# XIAO_ESP32S3_Exp_Board_v1_0.net
KiCad netlist of a schematic drawn in EAGLE
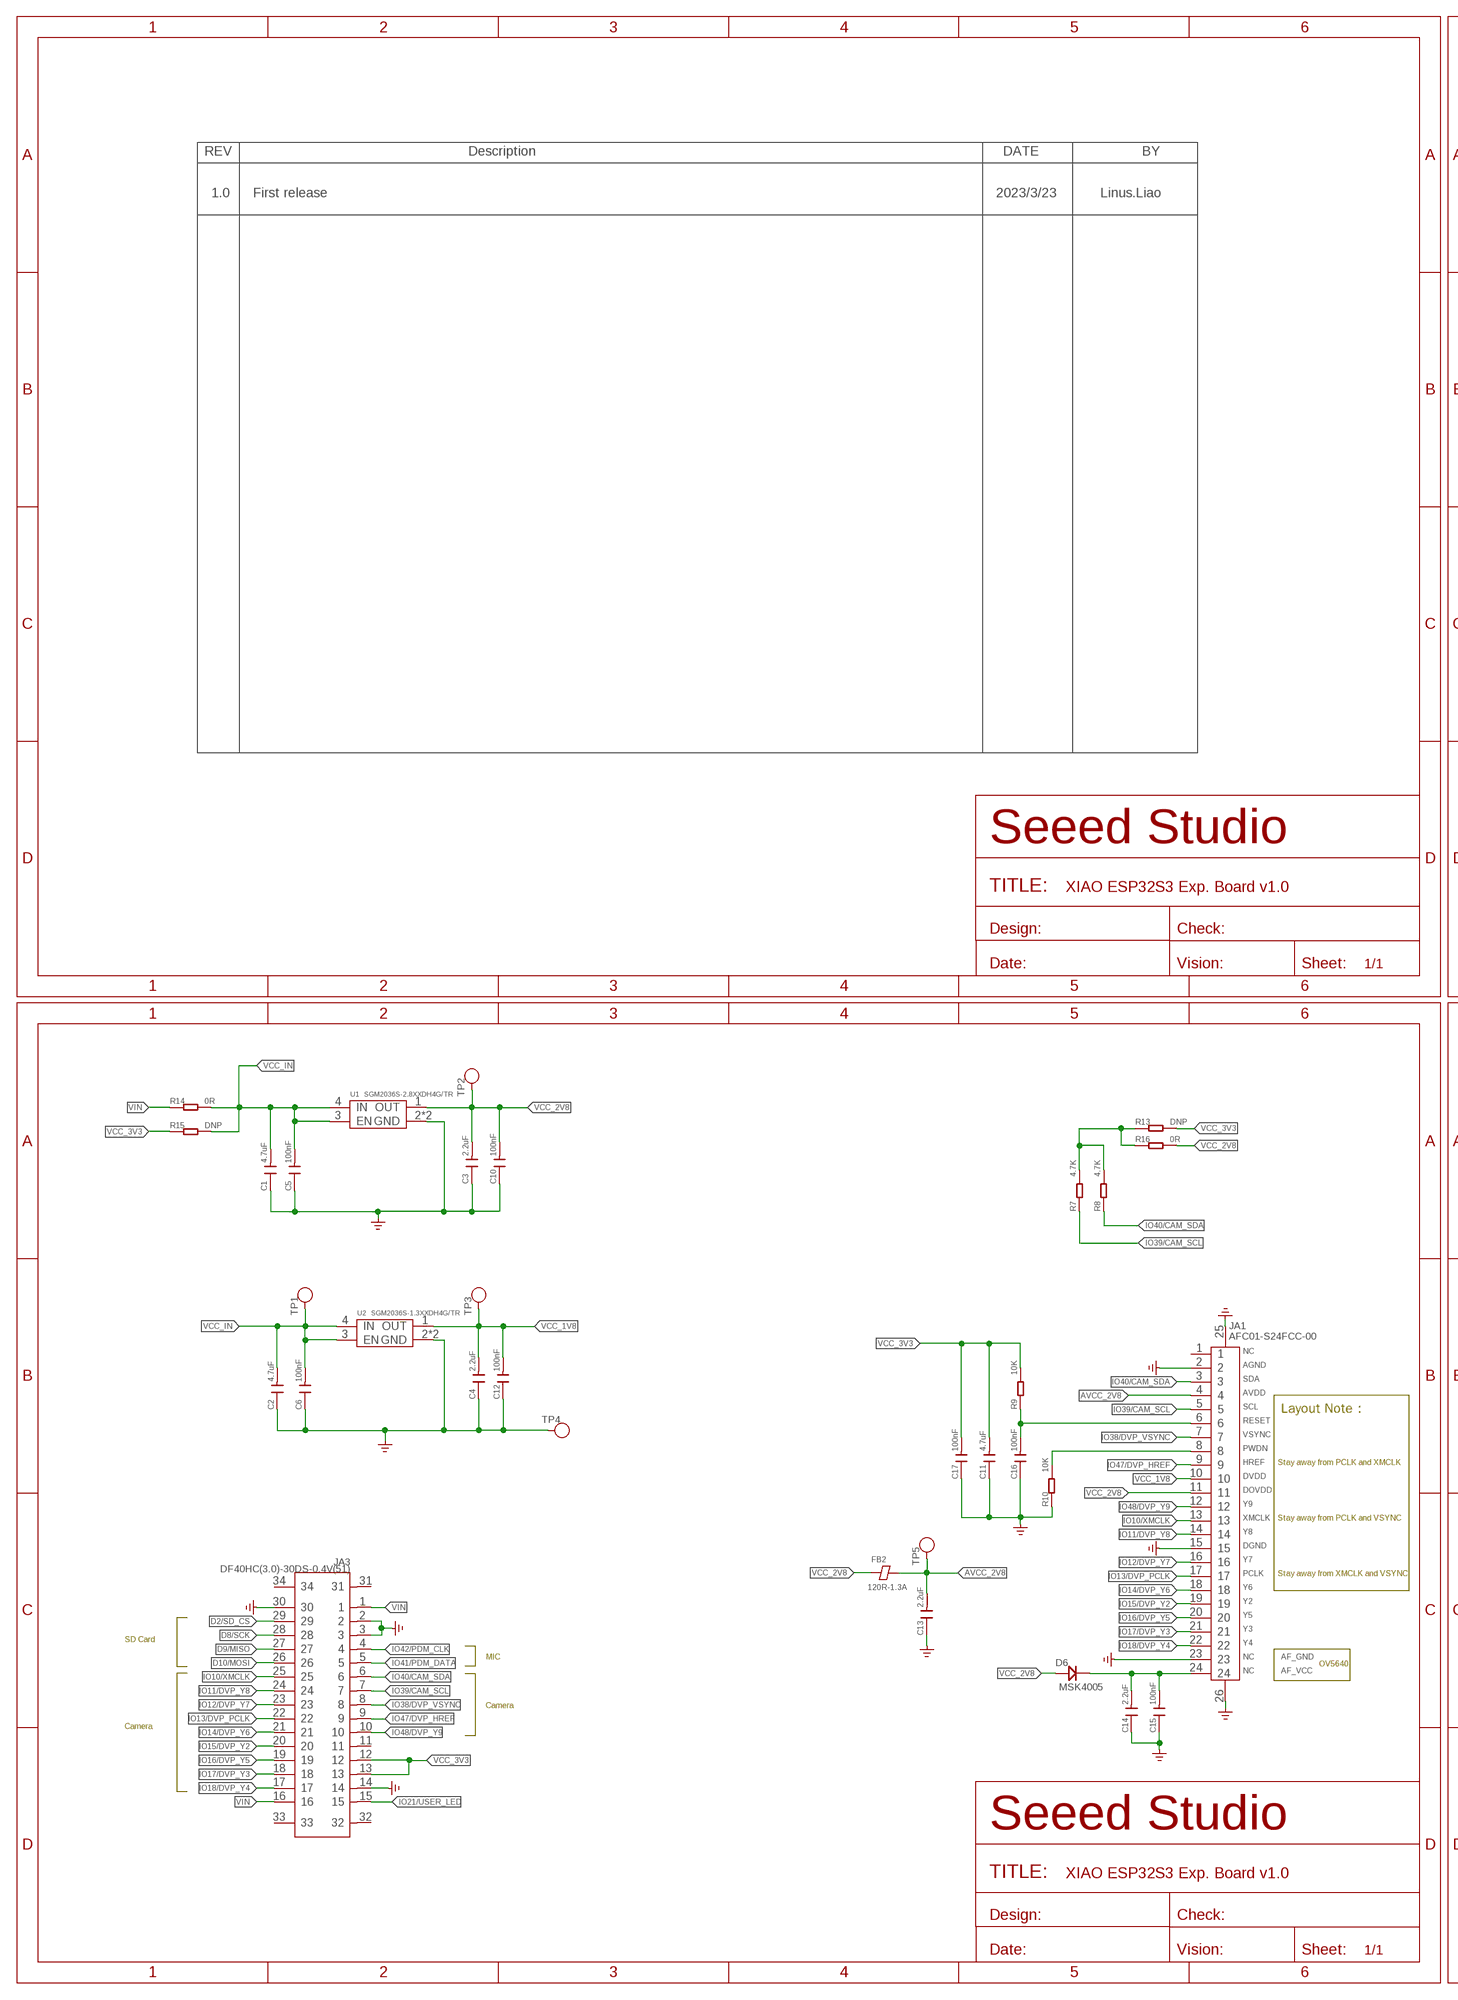
[diagram p0: schematic, sheet 1, part 1 of 2]
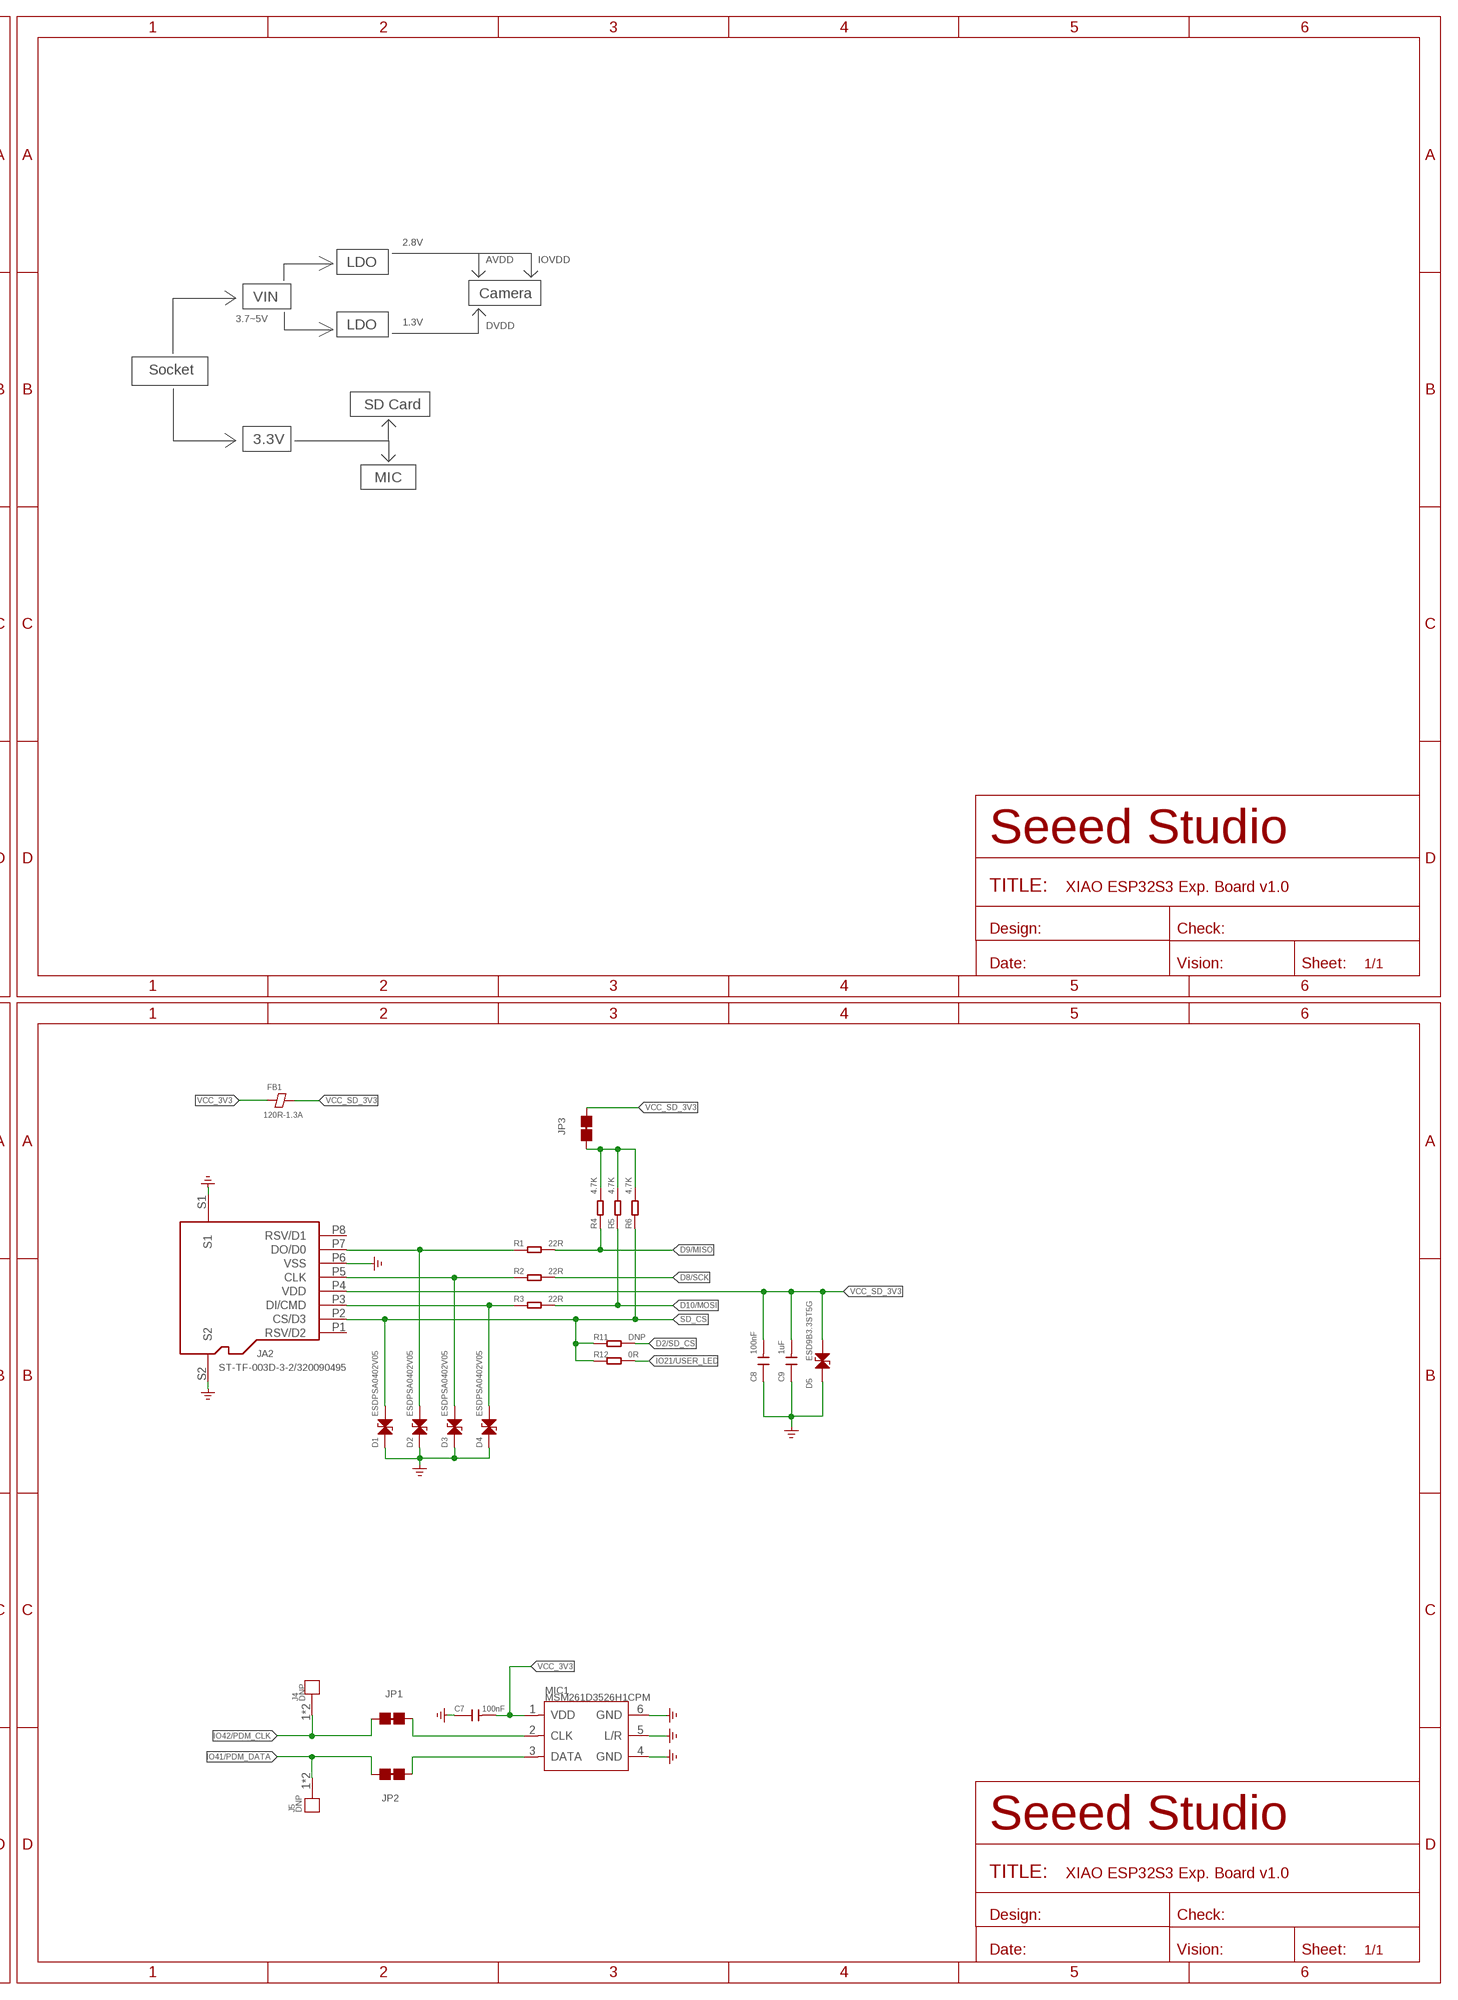
[diagram p1: schematic, sheet 1, part 2 of 2]

(export (version "E")
  (design (tool "Eeschema 10.0.6"))
  (components
    (comp (ref "C1")
      (value "4.7uF")
      (footprint "eagle-import:C0402")
      (libsource (lib "eagle-import") (part "C-0402"))
    )
    (comp (ref "C2")
      (value "4.7uF")
      (footprint "eagle-import:C0402")
      (libsource (lib "eagle-import") (part "C-0402"))
    )
    (comp (ref "C3")
      (value "2.2uF")
      (footprint "eagle-import:C0402")
      (libsource (lib "eagle-import") (part "C-0402"))
    )
    (comp (ref "C4")
      (value "2.2uF")
      (footprint "eagle-import:C0402")
      (libsource (lib "eagle-import") (part "C-0402"))
    )
    (comp (ref "C5")
      (value "100nF")
      (footprint "eagle-import:C0402")
      (libsource (lib "eagle-import") (part "C-0402"))
    )
    (comp (ref "C6")
      (value "100nF")
      (footprint "eagle-import:C0402")
      (libsource (lib "eagle-import") (part "C-0402"))
    )
    (comp (ref "C7")
      (value "100nF")
      (footprint "eagle-import:C0402")
      (libsource (lib "eagle-import") (part "C-0402"))
    )
    (comp (ref "C8")
      (value "100nF")
      (footprint "eagle-import:C0402")
      (libsource (lib "eagle-import") (part "C-0402"))
    )
    (comp (ref "C9")
      (value "1uF")
      (footprint "eagle-import:C0402")
      (libsource (lib "eagle-import") (part "C-0402"))
    )
    (comp (ref "C10")
      (value "100nF")
      (footprint "eagle-import:C0402")
      (libsource (lib "eagle-import") (part "C-0402"))
    )
    (comp (ref "C11")
      (value "4.7uF")
      (footprint "eagle-import:C0402")
      (libsource (lib "eagle-import") (part "C-0402"))
    )
    (comp (ref "C12")
      (value "100nF")
      (footprint "eagle-import:C0402")
      (libsource (lib "eagle-import") (part "C-0402"))
    )
    (comp (ref "C13")
      (value "2.2uF")
      (footprint "eagle-import:C0402")
      (libsource (lib "eagle-import") (part "C-0402"))
    )
    (comp (ref "C14")
      (value "2.2uF")
      (footprint "eagle-import:C0402")
      (libsource (lib "eagle-import") (part "C-0402"))
    )
    (comp (ref "C15")
      (value "100nF")
      (footprint "eagle-import:C0402")
      (libsource (lib "eagle-import") (part "C-0402"))
    )
    (comp (ref "C16")
      (value "100nF")
      (footprint "eagle-import:C0402")
      (libsource (lib "eagle-import") (part "C-0402"))
    )
    (comp (ref "C17")
      (value "100nF")
      (footprint "eagle-import:C0402")
      (libsource (lib "eagle-import") (part "C-0402"))
    )
    (comp (ref "D1")
      (value "ESDPSA0402V05")
      (footprint "eagle-import:ESD-0402-NO-SILK")
      (libsource (lib "eagle-import") (part "D-ESD-2P-DOUBLE"))
    )
    (comp (ref "D2")
      (value "ESDPSA0402V05")
      (footprint "eagle-import:ESD-0402-NO-SILK")
      (libsource (lib "eagle-import") (part "D-ESD-2P-DOUBLE"))
    )
    (comp (ref "D3")
      (value "ESDPSA0402V05")
      (footprint "eagle-import:ESD-0402-NO-SILK")
      (libsource (lib "eagle-import") (part "D-ESD-2P-DOUBLE"))
    )
    (comp (ref "D4")
      (value "ESDPSA0402V05")
      (footprint "eagle-import:ESD-0402-NO-SILK")
      (libsource (lib "eagle-import") (part "D-ESD-2P-DOUBLE"))
    )
    (comp (ref "D5")
      (value "ESD9B3.3ST5G")
      (footprint "eagle-import:ESD-0402-NO-SILK")
      (libsource (lib "eagle-import") (part "D-ESD-2P-DOUBLE"))
    )
    (comp (ref "D6")
      (value "MSK4005")
      (footprint "eagle-import:SOD-523")
      (libsource (lib "eagle-import") (part "DIODE'0603'"))
    )
    (comp (ref "FB1")
      (value "120R-1.3A")
      (footprint "eagle-import:F0402")
      (libsource (lib "eagle-import") (part "FERRITE-BEAD-0402"))
    )
    (comp (ref "FB2")
      (value "120R-1.3A")
      (footprint "eagle-import:F0402")
      (libsource (lib "eagle-import") (part "FERRITE-BEAD-0402"))
    )
    (comp (ref "J4")
      (value "DNP")
      (footprint "eagle-import:H1-HALF-HOLE-2.54")
      (libsource (lib "eagle-import") (part "HEADER-1P-HALF-HOLE"))
    )
    (comp (ref "J5")
      (value "DNP")
      (footprint "eagle-import:H1-HALF-HOLE-2.54")
      (libsource (lib "eagle-import") (part "HEADER-1P-HALF-HOLE"))
    )
    (comp (ref "JA1")
      (value "AFC01-S24FCC-00")
      (footprint "eagle-import:FPCB24-SMD-0.5-17.6X5.0X2MM")
      (libsource (lib "eagle-import") (part "FPC-CONNECTOR-24P"))
    )
    (comp (ref "JA2")
      (value "ST-TF-003D-3-2/320090495")
      (footprint "eagle-import:MICRO-SD8+2P-SMD-1.1-11.41X4.9X3MM")
      (libsource (lib "eagle-import") (part "MICRO-SD-CARD-HOLDER-SHORT-8P"))
    )
    (comp (ref "JA3")
      (value "DF40HC(3.0)-30DS-0.4V(51)")
      (footprint "eagle-import:BTB30-0.4-8.6X3.38X2.4MM")
      (libsource (lib "eagle-import") (part "BTB-P4S30DF40HC-SOCKET"))
    )
    (comp (ref "JP1")
      (value "JP-2P-SHORT")
      (footprint "eagle-import:2P-SMD-0603")
      (libsource (lib "eagle-import") (part "JP-2P-SHORT"))
    )
    (comp (ref "JP2")
      (value "JP-2P-SHORT")
      (footprint "eagle-import:2P-SMD-0603")
      (libsource (lib "eagle-import") (part "JP-2P-SHORT"))
    )
    (comp (ref "JP3")
      (value "JP-2P-SHORT")
      (footprint "eagle-import:2P-SMD-0603")
      (libsource (lib "eagle-import") (part "JP-2P-SHORT"))
    )
    (comp (ref "MIC1")
      (value "MSM261D3526H1CPM")
      (footprint "eagle-import:MIC6P-3.5X2.65X0.94MM")
      (libsource (lib "eagle-import") (part "MIC-MSM261D3526H1CPM"))
    )
    (comp (ref "R1")
      (value "22R")
      (footprint "eagle-import:R0402")
      (libsource (lib "eagle-import") (part "R-0402"))
    )
    (comp (ref "R2")
      (value "22R")
      (footprint "eagle-import:R0402")
      (libsource (lib "eagle-import") (part "R-0402"))
    )
    (comp (ref "R3")
      (value "22R")
      (footprint "eagle-import:R0402")
      (libsource (lib "eagle-import") (part "R-0402"))
    )
    (comp (ref "R4")
      (value "4.7K")
      (footprint "eagle-import:R0402")
      (libsource (lib "eagle-import") (part "R-0402"))
    )
    (comp (ref "R5")
      (value "4.7K")
      (footprint "eagle-import:R0402")
      (libsource (lib "eagle-import") (part "R-0402"))
    )
    (comp (ref "R6")
      (value "4.7K")
      (footprint "eagle-import:R0402")
      (libsource (lib "eagle-import") (part "R-0402"))
    )
    (comp (ref "R7")
      (value "4.7K")
      (footprint "eagle-import:R0402")
      (libsource (lib "eagle-import") (part "R-0402"))
    )
    (comp (ref "R8")
      (value "4.7K")
      (footprint "eagle-import:R0402")
      (libsource (lib "eagle-import") (part "R-0402"))
    )
    (comp (ref "R9")
      (value "10K")
      (footprint "eagle-import:R0402")
      (libsource (lib "eagle-import") (part "R-0402"))
    )
    (comp (ref "R10")
      (value "10K")
      (footprint "eagle-import:R0402")
      (libsource (lib "eagle-import") (part "R-0402"))
    )
    (comp (ref "R11")
      (value "DNP")
      (footprint "eagle-import:R0402")
      (libsource (lib "eagle-import") (part "R-0402"))
    )
    (comp (ref "R12")
      (value "0R")
      (footprint "eagle-import:R0402")
      (libsource (lib "eagle-import") (part "R-0402"))
    )
    (comp (ref "R13")
      (value "DNP")
      (footprint "eagle-import:R0402")
      (libsource (lib "eagle-import") (part "R-0402"))
    )
    (comp (ref "R14")
      (value "0R")
      (footprint "eagle-import:R0402")
      (libsource (lib "eagle-import") (part "R-0402"))
    )
    (comp (ref "R15")
      (value "DNP")
      (footprint "eagle-import:R0402")
      (libsource (lib "eagle-import") (part "R-0402"))
    )
    (comp (ref "R16")
      (value "0R")
      (footprint "eagle-import:R0402")
      (libsource (lib "eagle-import") (part "R-0402"))
    )
    (comp (ref "TP1")
      (value "TEST-POINT-35")
      (footprint "eagle-import:TP_3535")
      (libsource (lib "eagle-import") (part "TEST-POINT-35"))
    )
    (comp (ref "TP2")
      (value "TEST-POINT-35")
      (footprint "eagle-import:TP_3535")
      (libsource (lib "eagle-import") (part "TEST-POINT-35"))
    )
    (comp (ref "TP3")
      (value "TEST-POINT-35")
      (footprint "eagle-import:TP_3535")
      (libsource (lib "eagle-import") (part "TEST-POINT-35"))
    )
    (comp (ref "TP4")
      (value "TEST-POINT-35")
      (footprint "eagle-import:TP_3535")
      (libsource (lib "eagle-import") (part "TEST-POINT-35"))
    )
    (comp (ref "TP5")
      (value "TEST-POINT-35")
      (footprint "eagle-import:TP_3535")
      (libsource (lib "eagle-import") (part "TEST-POINT-35"))
    )
    (comp (ref "U1")
      (value "SGM2036S-2.8XXDH4G/TR")
      (footprint "eagle-import:X2SON-4")
      (libsource (lib "eagle-import") (part "TLV733P"))
    )
    (comp (ref "U2")
      (value "SGM2036S-1.3XXDH4G/TR")
      (footprint "eagle-import:X2SON-4")
      (libsource (lib "eagle-import") (part "TLV733P"))
    )
  )
  (nets
    (net (code "1") (name "AVCC_2V8") (class "Default")
      (node (ref "C13") (pin "2") (pinfunction "2_2") (pintype "passive"))
      (node (ref "FB2") (pin "2") (pinfunction "2_2") (pintype "bidirectional"))
      (node (ref "JA1") (pin "4") (pinfunction "4_4") (pintype "bidirectional"))
      (node (ref "TP5") (pin "T") (pinfunction "T_T") (pintype "bidirectional"))
    )
    (net (code "2") (name "D2{slash}SD_CS") (class "Default")
      (node (ref "JA3") (pin "29") (pinfunction "29_29") (pintype "bidirectional"))
      (node (ref "R11") (pin "2") (pinfunction "2_2") (pintype "passive"))
    )
    (net (code "3") (name "D8{slash}SCK") (class "Default")
      (node (ref "JA3") (pin "28") (pinfunction "28_28") (pintype "bidirectional"))
      (node (ref "R2") (pin "2") (pinfunction "2_2") (pintype "passive"))
    )
    (net (code "4") (name "D9{slash}MISO") (class "Default")
      (node (ref "JA3") (pin "27") (pinfunction "27_27") (pintype "bidirectional"))
      (node (ref "R1") (pin "2") (pinfunction "2_2") (pintype "passive"))
      (node (ref "R4") (pin "1") (pinfunction "1_1") (pintype "passive"))
    )
    (net (code "5") (name "D10{slash}MOSI") (class "Default")
      (node (ref "JA3") (pin "26") (pinfunction "26_26") (pintype "bidirectional"))
      (node (ref "R3") (pin "2") (pinfunction "2_2") (pintype "passive"))
      (node (ref "R5") (pin "1") (pinfunction "1_1") (pintype "passive"))
    )
    (net (code "6") (name "GND_POWER") (class "Default")
      (node (ref "C1") (pin "1") (pinfunction "1_1") (pintype "passive"))
      (node (ref "C10") (pin "1") (pinfunction "1_1") (pintype "passive"))
      (node (ref "C11") (pin "1") (pinfunction "1_1") (pintype "passive"))
      (node (ref "C12") (pin "1") (pinfunction "1_1") (pintype "passive"))
      (node (ref "C13") (pin "1") (pinfunction "1_1") (pintype "passive"))
      (node (ref "C14") (pin "1") (pinfunction "1_1") (pintype "passive"))
      (node (ref "C15") (pin "1") (pinfunction "1_1") (pintype "passive"))
      (node (ref "C16") (pin "1") (pinfunction "1_1") (pintype "passive"))
      (node (ref "C17") (pin "1") (pinfunction "1_1") (pintype "passive"))
      (node (ref "C2") (pin "1") (pinfunction "1_1") (pintype "passive"))
      (node (ref "C3") (pin "1") (pinfunction "1_1") (pintype "passive"))
      (node (ref "C4") (pin "1") (pinfunction "1_1") (pintype "passive"))
      (node (ref "C5") (pin "1") (pinfunction "1_1") (pintype "passive"))
      (node (ref "C6") (pin "1") (pinfunction "1_1") (pintype "passive"))
      (node (ref "C7") (pin "1") (pinfunction "1_1") (pintype "passive"))
      (node (ref "C8") (pin "1") (pinfunction "1_1") (pintype "passive"))
      (node (ref "C9") (pin "1") (pinfunction "1_1") (pintype "passive"))
      (node (ref "D1") (pin "1") (pinfunction "1_1") (pintype "bidirectional"))
      (node (ref "D2") (pin "1") (pinfunction "1_1") (pintype "bidirectional"))
      (node (ref "D3") (pin "1") (pinfunction "1_1") (pintype "bidirectional"))
      (node (ref "D4") (pin "1") (pinfunction "1_1") (pintype "bidirectional"))
      (node (ref "D5") (pin "1") (pinfunction "1_1") (pintype "bidirectional"))
      (node (ref "JA1") (pin "15") (pinfunction "15_15") (pintype "bidirectional"))
      (node (ref "JA1") (pin "2") (pinfunction "2_2") (pintype "bidirectional"))
      (node (ref "JA1") (pin "23") (pinfunction "23_23") (pintype "bidirectional"))
      (node (ref "JA1") (pin "25") (pinfunction "P1_25") (pintype "bidirectional"))
      (node (ref "JA1") (pin "26") (pinfunction "P2_26") (pintype "bidirectional"))
      (node (ref "JA2") (pin "P6") (pinfunction "VSS_P6") (pintype "bidirectional"))
      (node (ref "JA2") (pin "S1") (pinfunction "S1_S1") (pintype "bidirectional"))
      (node (ref "JA2") (pin "S2") (pinfunction "S2_S2") (pintype "bidirectional"))
      (node (ref "JA3") (pin "14") (pinfunction "14_14") (pintype "bidirectional"))
      (node (ref "JA3") (pin "2") (pinfunction "2_2") (pintype "bidirectional"))
      (node (ref "JA3") (pin "3") (pinfunction "3_3") (pintype "bidirectional"))
      (node (ref "JA3") (pin "30") (pinfunction "30_30") (pintype "bidirectional"))
      (node (ref "MIC1") (pin "4") (pinfunction "GND_4") (pintype "bidirectional"))
      (node (ref "MIC1") (pin "5") (pinfunction "L/R_5") (pintype "bidirectional"))
      (node (ref "MIC1") (pin "6") (pinfunction "GND_6") (pintype "bidirectional"))
      (node (ref "R10") (pin "1") (pinfunction "1_1") (pintype "passive"))
      (node (ref "TP4") (pin "T") (pinfunction "T_T") (pintype "bidirectional"))
      (node (ref "U1") (pin "2") (pinfunction "GND_2") (pintype "bidirectional"))
      (node (ref "U1") (pin "T") (pinfunction "GND_T") (pintype "bidirectional"))
      (node (ref "U2") (pin "2") (pinfunction "GND_2") (pintype "bidirectional"))
      (node (ref "U2") (pin "T") (pinfunction "GND_T") (pintype "bidirectional"))
    )
    (net (code "7") (name "IO10{slash}XMCLK") (class "Default")
      (node (ref "JA1") (pin "13") (pinfunction "13_13") (pintype "bidirectional"))
      (node (ref "JA3") (pin "25") (pinfunction "25_25") (pintype "bidirectional"))
    )
    (net (code "8") (name "IO11{slash}DVP_Y8") (class "Default")
      (node (ref "JA1") (pin "14") (pinfunction "14_14") (pintype "bidirectional"))
      (node (ref "JA3") (pin "24") (pinfunction "24_24") (pintype "bidirectional"))
    )
    (net (code "9") (name "IO12{slash}DVP_Y7") (class "Default")
      (node (ref "JA1") (pin "16") (pinfunction "16_16") (pintype "bidirectional"))
      (node (ref "JA3") (pin "23") (pinfunction "23_23") (pintype "bidirectional"))
    )
    (net (code "10") (name "IO13{slash}DVP_PCLK") (class "Default")
      (node (ref "JA1") (pin "17") (pinfunction "17_17") (pintype "bidirectional"))
      (node (ref "JA3") (pin "22") (pinfunction "22_22") (pintype "bidirectional"))
    )
    (net (code "11") (name "IO14{slash}DVP_Y6") (class "Default")
      (node (ref "JA1") (pin "18") (pinfunction "18_18") (pintype "bidirectional"))
      (node (ref "JA3") (pin "21") (pinfunction "21_21") (pintype "bidirectional"))
    )
    (net (code "12") (name "IO15{slash}DVP_Y2") (class "Default")
      (node (ref "JA1") (pin "19") (pinfunction "19_19") (pintype "bidirectional"))
      (node (ref "JA3") (pin "20") (pinfunction "20_20") (pintype "bidirectional"))
    )
    (net (code "13") (name "IO16{slash}DVP_Y5") (class "Default")
      (node (ref "JA1") (pin "20") (pinfunction "20_20") (pintype "bidirectional"))
      (node (ref "JA3") (pin "19") (pinfunction "19_19") (pintype "bidirectional"))
    )
    (net (code "14") (name "IO17{slash}DVP_Y3") (class "Default")
      (node (ref "JA1") (pin "21") (pinfunction "21_21") (pintype "bidirectional"))
      (node (ref "JA3") (pin "18") (pinfunction "18_18") (pintype "bidirectional"))
    )
    (net (code "15") (name "IO18{slash}DVP_Y4") (class "Default")
      (node (ref "JA1") (pin "22") (pinfunction "22_22") (pintype "bidirectional"))
      (node (ref "JA3") (pin "17") (pinfunction "17_17") (pintype "bidirectional"))
    )
    (net (code "16") (name "IO21{slash}USER_LED") (class "Default")
      (node (ref "JA3") (pin "15") (pinfunction "15_15") (pintype "bidirectional"))
      (node (ref "R12") (pin "2") (pinfunction "2_2") (pintype "passive"))
    )
    (net (code "17") (name "IO38{slash}DVP_VSYNC") (class "Default")
      (node (ref "JA1") (pin "7") (pinfunction "7_7") (pintype "bidirectional"))
      (node (ref "JA3") (pin "8") (pinfunction "8_8") (pintype "bidirectional"))
    )
    (net (code "18") (name "IO39{slash}CAM_SCL") (class "Default")
      (node (ref "JA1") (pin "5") (pinfunction "5_5") (pintype "bidirectional"))
      (node (ref "JA3") (pin "7") (pinfunction "7_7") (pintype "bidirectional"))
      (node (ref "R7") (pin "1") (pinfunction "1_1") (pintype "passive"))
    )
    (net (code "19") (name "IO40{slash}CAM_SDA") (class "Default")
      (node (ref "JA1") (pin "3") (pinfunction "3_3") (pintype "bidirectional"))
      (node (ref "JA3") (pin "6") (pinfunction "6_6") (pintype "bidirectional"))
      (node (ref "R8") (pin "1") (pinfunction "1_1") (pintype "passive"))
    )
    (net (code "20") (name "IO41{slash}PDM_DATA") (class "Default")
      (node (ref "J5") (pin "1") (pinfunction "1_1") (pintype "bidirectional"))
      (node (ref "J5") (pin "2") (pinfunction "1_2") (pintype "bidirectional"))
      (node (ref "JA3") (pin "5") (pinfunction "5_5") (pintype "bidirectional"))
      (node (ref "JP2") (pin "P2") (pinfunction "2_P2") (pintype "bidirectional"))
    )
    (net (code "21") (name "IO42{slash}PDM_CLK") (class "Default")
      (node (ref "J4") (pin "1") (pinfunction "1_1") (pintype "bidirectional"))
      (node (ref "J4") (pin "2") (pinfunction "1_2") (pintype "bidirectional"))
      (node (ref "JA3") (pin "4") (pinfunction "4_4") (pintype "bidirectional"))
      (node (ref "JP1") (pin "P1") (pinfunction "1_P1") (pintype "bidirectional"))
    )
    (net (code "22") (name "IO47{slash}DVP_HREF") (class "Default")
      (node (ref "JA1") (pin "9") (pinfunction "9_9") (pintype "bidirectional"))
      (node (ref "JA3") (pin "9") (pinfunction "9_9") (pintype "bidirectional"))
    )
    (net (code "23") (name "IO48{slash}DVP_Y9") (class "Default")
      (node (ref "JA1") (pin "12") (pinfunction "12_12") (pintype "bidirectional"))
      (node (ref "JA3") (pin "10") (pinfunction "10_10") (pintype "bidirectional"))
    )
    (net (code "24") (name "Net-(C14-Pad2)") (class "Default")
      (node (ref "C14") (pin "2") (pinfunction "2_2") (pintype "passive"))
      (node (ref "C15") (pin "2") (pinfunction "2_2") (pintype "passive"))
      (node (ref "D6") (pin "-") (pinfunction "-_-") (pintype "passive"))
      (node (ref "JA1") (pin "24") (pinfunction "24_24") (pintype "bidirectional"))
    )
    (net (code "25") (name "Net-(C16-Pad2)") (class "Default")
      (node (ref "C16") (pin "2") (pinfunction "2_2") (pintype "passive"))
      (node (ref "JA1") (pin "6") (pinfunction "6_6") (pintype "bidirectional"))
      (node (ref "R9") (pin "1") (pinfunction "1_1") (pintype "passive"))
    )
    (net (code "26") (name "Net-(JA1-Pad8)") (class "Default")
      (node (ref "JA1") (pin "8") (pinfunction "8_8") (pintype "bidirectional"))
      (node (ref "R10") (pin "2") (pinfunction "2_2") (pintype "passive"))
    )
    (net (code "27") (name "Net-(JA2-CLK)") (class "Default")
      (node (ref "D3") (pin "2") (pinfunction "2_2") (pintype "bidirectional"))
      (node (ref "JA2") (pin "P5") (pinfunction "CLK_P5") (pintype "bidirectional"))
      (node (ref "R2") (pin "1") (pinfunction "1_1") (pintype "passive"))
    )
    (net (code "28") (name "Net-(JA2-DI{slash}CMD)") (class "Default")
      (node (ref "D4") (pin "2") (pinfunction "2_2") (pintype "bidirectional"))
      (node (ref "JA2") (pin "P3") (pinfunction "DI/CMD_P3") (pintype "bidirectional"))
      (node (ref "R3") (pin "1") (pinfunction "1_1") (pintype "passive"))
    )
    (net (code "29") (name "Net-(JA2-DO{slash}D0)") (class "Default")
      (node (ref "D2") (pin "2") (pinfunction "2_2") (pintype "bidirectional"))
      (node (ref "JA2") (pin "P7") (pinfunction "DO/D0_P7") (pintype "bidirectional"))
      (node (ref "R1") (pin "1") (pinfunction "1_1") (pintype "passive"))
    )
    (net (code "30") (name "Net-(JP1-2)") (class "Default")
      (node (ref "JP1") (pin "P2") (pinfunction "2_P2") (pintype "bidirectional"))
      (node (ref "MIC1") (pin "2") (pinfunction "CLK_2") (pintype "bidirectional"))
    )
    (net (code "31") (name "Net-(JP2-1)") (class "Default")
      (node (ref "JP2") (pin "P1") (pinfunction "1_P1") (pintype "bidirectional"))
      (node (ref "MIC1") (pin "3") (pinfunction "DATA_3") (pintype "bidirectional"))
    )
    (net (code "32") (name "Net-(JP3-1)") (class "Default")
      (node (ref "JP3") (pin "P1") (pinfunction "1_P1") (pintype "bidirectional"))
      (node (ref "R4") (pin "2") (pinfunction "2_2") (pintype "passive"))
      (node (ref "R5") (pin "2") (pinfunction "2_2") (pintype "passive"))
      (node (ref "R6") (pin "2") (pinfunction "2_2") (pintype "passive"))
    )
    (net (code "33") (name "Net-(R13-Pad1)") (class "Default")
      (node (ref "R13") (pin "1") (pinfunction "1_1") (pintype "passive"))
      (node (ref "R16") (pin "1") (pinfunction "1_1") (pintype "passive"))
      (node (ref "R7") (pin "2") (pinfunction "2_2") (pintype "passive"))
      (node (ref "R8") (pin "2") (pinfunction "2_2") (pintype "passive"))
    )
    (net (code "34") (name "SD_CS") (class "Default")
      (node (ref "D1") (pin "2") (pinfunction "2_2") (pintype "bidirectional"))
      (node (ref "JA2") (pin "P2") (pinfunction "CS/D3_P2") (pintype "bidirectional"))
      (node (ref "R11") (pin "1") (pinfunction "1_1") (pintype "passive"))
      (node (ref "R12") (pin "1") (pinfunction "1_1") (pintype "passive"))
      (node (ref "R6") (pin "1") (pinfunction "1_1") (pintype "passive"))
    )
    (net (code "35") (name "VCC_1V8") (class "Default")
      (node (ref "C12") (pin "2") (pinfunction "2_2") (pintype "passive"))
      (node (ref "C4") (pin "2") (pinfunction "2_2") (pintype "passive"))
      (node (ref "JA1") (pin "10") (pinfunction "10_10") (pintype "bidirectional"))
      (node (ref "TP3") (pin "T") (pinfunction "T_T") (pintype "bidirectional"))
      (node (ref "U2") (pin "1") (pinfunction "OUT_1") (pintype "bidirectional"))
    )
    (net (code "36") (name "VCC_2V8") (class "Default")
      (node (ref "C10") (pin "2") (pinfunction "2_2") (pintype "passive"))
      (node (ref "C3") (pin "2") (pinfunction "2_2") (pintype "passive"))
      (node (ref "D6") (pin "+") (pinfunction "+_+") (pintype "passive"))
      (node (ref "FB2") (pin "1") (pinfunction "1_1") (pintype "bidirectional"))
      (node (ref "JA1") (pin "11") (pinfunction "11_11") (pintype "bidirectional"))
      (node (ref "R16") (pin "2") (pinfunction "2_2") (pintype "passive"))
      (node (ref "TP2") (pin "T") (pinfunction "T_T") (pintype "bidirectional"))
      (node (ref "U1") (pin "1") (pinfunction "OUT_1") (pintype "bidirectional"))
    )
    (net (code "37") (name "VCC_3V3") (class "Default")
      (node (ref "C11") (pin "2") (pinfunction "2_2") (pintype "passive"))
      (node (ref "C17") (pin "2") (pinfunction "2_2") (pintype "passive"))
      (node (ref "C7") (pin "2") (pinfunction "2_2") (pintype "passive"))
      (node (ref "FB1") (pin "1") (pinfunction "1_1") (pintype "bidirectional"))
      (node (ref "JA3") (pin "12") (pinfunction "12_12") (pintype "bidirectional"))
      (node (ref "JA3") (pin "13") (pinfunction "13_13") (pintype "bidirectional"))
      (node (ref "MIC1") (pin "1") (pinfunction "VDD_1") (pintype "bidirectional"))
      (node (ref "R13") (pin "2") (pinfunction "2_2") (pintype "passive"))
      (node (ref "R15") (pin "1") (pinfunction "1_1") (pintype "passive"))
      (node (ref "R9") (pin "2") (pinfunction "2_2") (pintype "passive"))
    )
    (net (code "38") (name "VCC_IN") (class "Default")
      (node (ref "C1") (pin "2") (pinfunction "2_2") (pintype "passive"))
      (node (ref "C2") (pin "2") (pinfunction "2_2") (pintype "passive"))
      (node (ref "C5") (pin "2") (pinfunction "2_2") (pintype "passive"))
      (node (ref "C6") (pin "2") (pinfunction "2_2") (pintype "passive"))
      (node (ref "R14") (pin "2") (pinfunction "2_2") (pintype "passive"))
      (node (ref "R15") (pin "2") (pinfunction "2_2") (pintype "passive"))
      (node (ref "TP1") (pin "T") (pinfunction "T_T") (pintype "bidirectional"))
      (node (ref "U1") (pin "3") (pinfunction "EN_3") (pintype "bidirectional"))
      (node (ref "U1") (pin "4") (pinfunction "IN_4") (pintype "bidirectional"))
      (node (ref "U2") (pin "3") (pinfunction "EN_3") (pintype "bidirectional"))
      (node (ref "U2") (pin "4") (pinfunction "IN_4") (pintype "bidirectional"))
    )
    (net (code "39") (name "VCC_SD_3V3") (class "Default")
      (node (ref "C8") (pin "2") (pinfunction "2_2") (pintype "passive"))
      (node (ref "C9") (pin "2") (pinfunction "2_2") (pintype "passive"))
      (node (ref "D5") (pin "2") (pinfunction "2_2") (pintype "bidirectional"))
      (node (ref "FB1") (pin "2") (pinfunction "2_2") (pintype "bidirectional"))
      (node (ref "JA2") (pin "P4") (pinfunction "VDD_P4") (pintype "bidirectional"))
      (node (ref "JP3") (pin "P2") (pinfunction "2_P2") (pintype "bidirectional"))
    )
    (net (code "40") (name "VIN") (class "Default")
      (node (ref "JA3") (pin "1") (pinfunction "1_1") (pintype "bidirectional"))
      (node (ref "JA3") (pin "16") (pinfunction "16_16") (pintype "bidirectional"))
      (node (ref "R14") (pin "1") (pinfunction "1_1") (pintype "passive"))
    )
    (net (code "41") (name "unconnected-(JA1-Pad1)") (class "Default")
      (node (ref "JA1") (pin "1") (pinfunction "1_1") (pintype "bidirectional"))
    )
    (net (code "42") (name "unconnected-(JA2-RSV{slash}D1-PadP8)") (class "Default")
      (node (ref "JA2") (pin "P8") (pinfunction "RSV/D1_P8") (pintype "bidirectional"))
    )
    (net (code "43") (name "unconnected-(JA2-RSV{slash}D2-PadP1)") (class "Default")
      (node (ref "JA2") (pin "P1") (pinfunction "RSV/D2_P1") (pintype "bidirectional"))
    )
    (net (code "44") (name "unconnected-(JA3-Pad11)") (class "Default")
      (node (ref "JA3") (pin "11") (pinfunction "11_11") (pintype "bidirectional"))
    )
    (net (code "45") (name "unconnected-(JA3-Pad31)") (class "Default")
      (node (ref "JA3") (pin "31") (pinfunction "31_31") (pintype "bidirectional"))
    )
    (net (code "46") (name "unconnected-(JA3-Pad32)") (class "Default")
      (node (ref "JA3") (pin "32") (pinfunction "32_32") (pintype "bidirectional"))
    )
    (net (code "47") (name "unconnected-(JA3-Pad33)") (class "Default")
      (node (ref "JA3") (pin "33") (pinfunction "33_33") (pintype "bidirectional"))
    )
    (net (code "48") (name "unconnected-(JA3-Pad34)") (class "Default")
      (node (ref "JA3") (pin "34") (pinfunction "34_34") (pintype "bidirectional"))
    )
  )
)
